# MEGA2560_Rev3e_1.net
KiCad netlist of a schematic drawn in Altium Designer
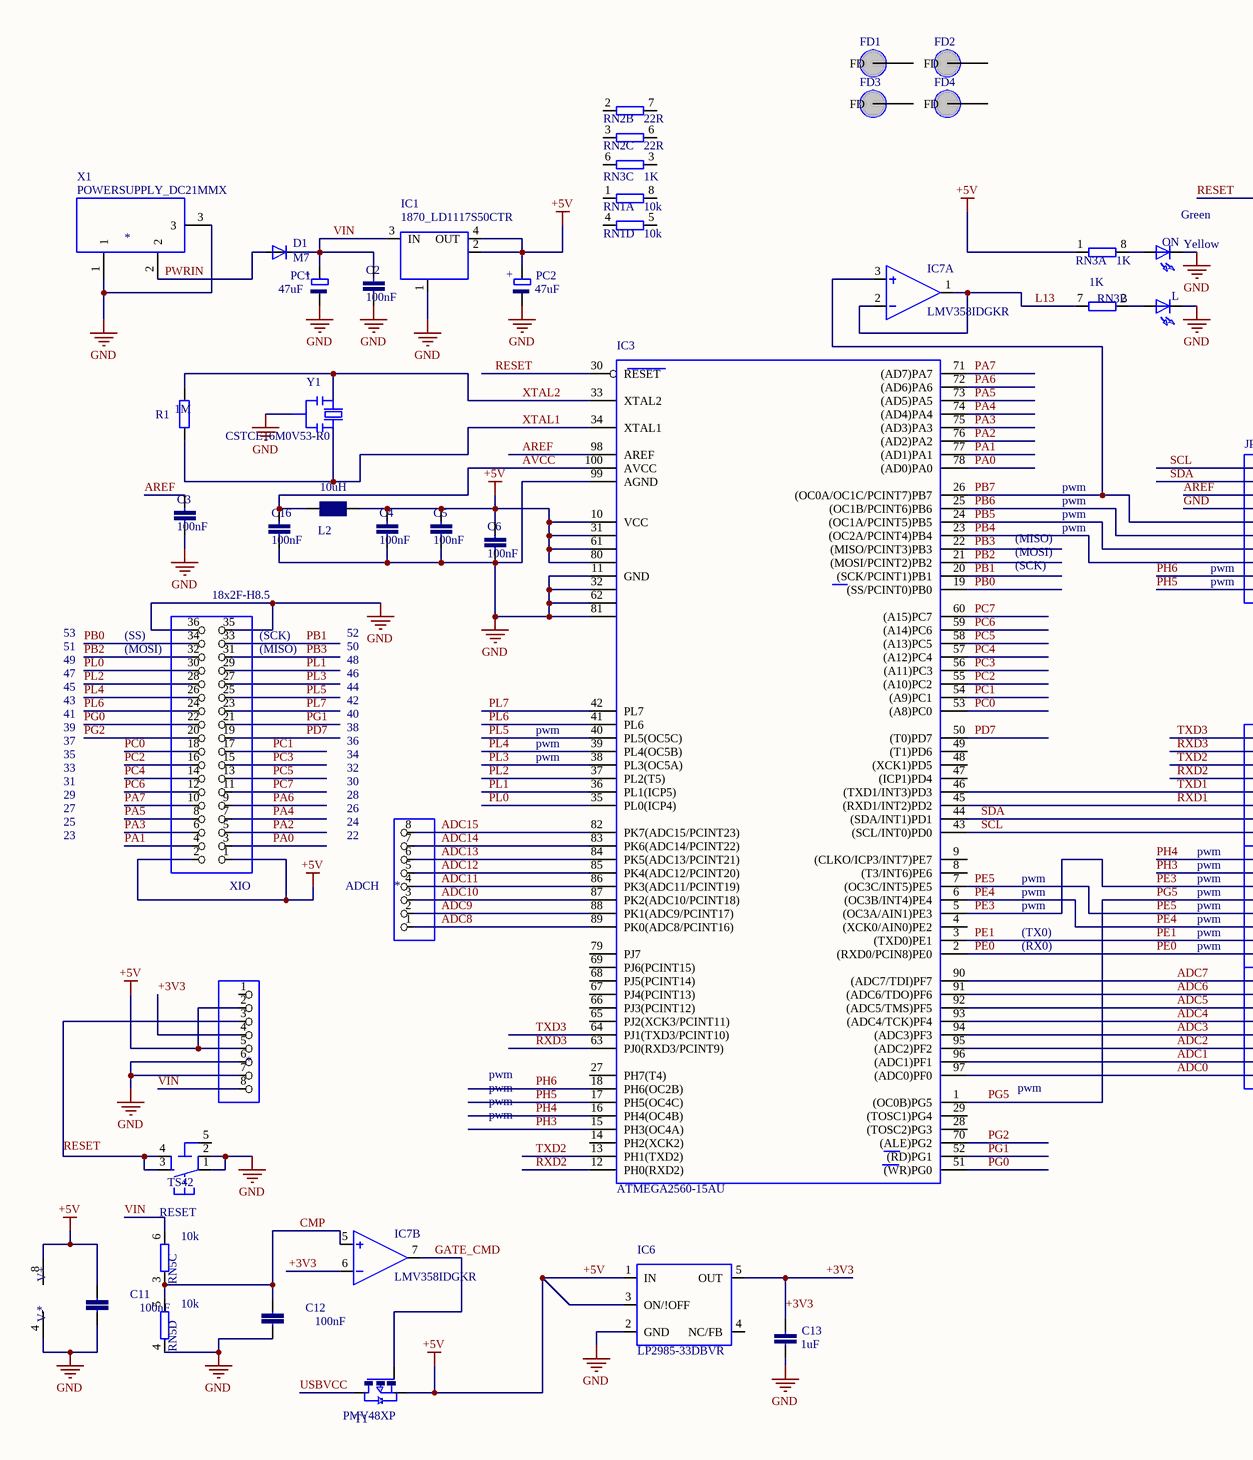
[diagram p0: MEGA2560_Rev3e_1.SchDoc, left]
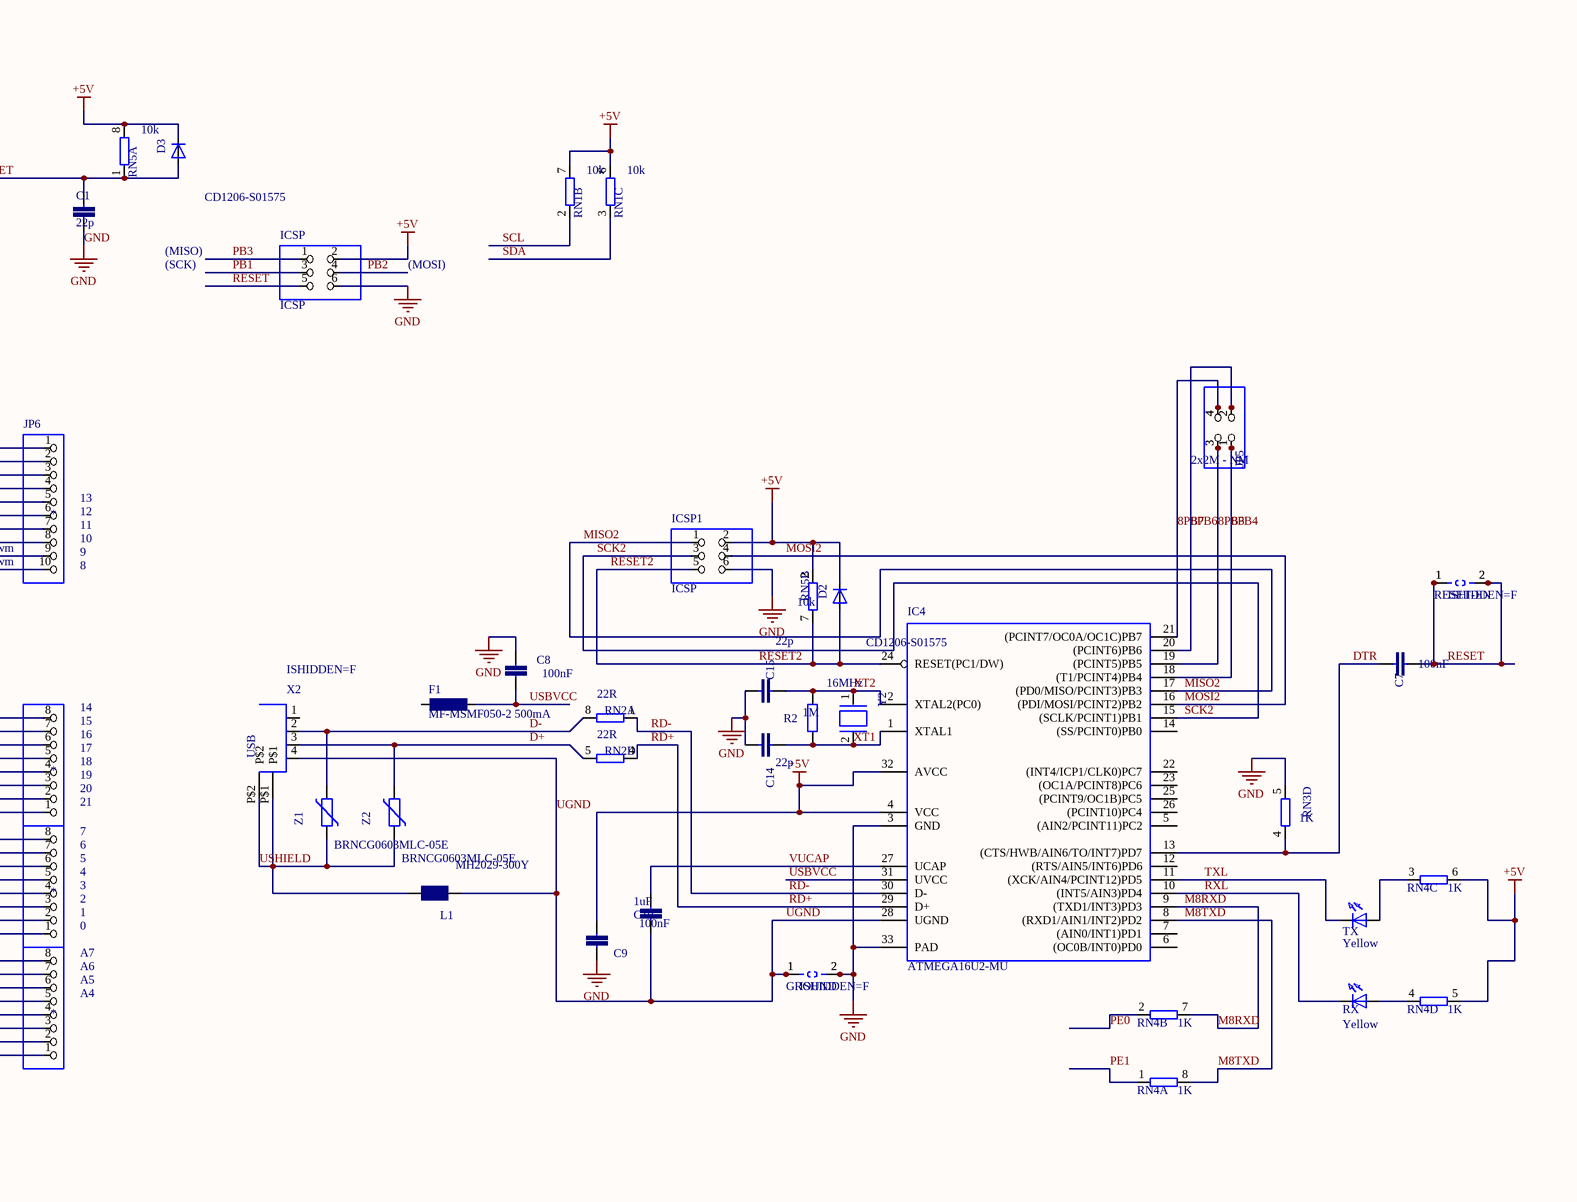
[diagram p1: MEGA2560_Rev3e_1.SchDoc, right]

(export (version "E")
  (design (tool "Eeschema 10.0.6"))
  (components
    (comp (ref "ADCH")
      (value "*")
      (footprint "1X08")
      (libsource (lib "Connettori") (part "0058_FH254-108DF08500V"))
    )
    (comp (ref "ADCL")
      (value "*")
      (footprint "1X08")
      (libsource (lib "Connettori") (part "0058_FH254-108DF08500V"))
    )
    (comp (ref "C1") (value "22p") (footprint "C0603-ROUND") (libsource (lib "") (part "0014_22PF_0603_1")))
    (comp (ref "C2")
      (value "100nF")
      (footprint "C0603-ROUND")
      (libsource (lib "Condensatori") (part "0015_100NF_0603"))
    )
    (comp (ref "C3")
      (value "100nF")
      (footprint "C0603-ROUND")
      (libsource (lib "Condensatori") (part "0015_100NF_0603"))
    )
    (comp (ref "C4")
      (value "100nF")
      (footprint "C0603-ROUND")
      (libsource (lib "Condensatori") (part "0015_100NF_0603"))
    )
    (comp (ref "C5")
      (value "100nF")
      (footprint "C0603-ROUND")
      (libsource (lib "Condensatori") (part "0015_100NF_0603"))
    )
    (comp (ref "C6")
      (value "100nF")
      (footprint "C0603-ROUND")
      (libsource (lib "Condensatori") (part "0015_100NF_0603"))
    )
    (comp (ref "C7")
      (value "100nF")
      (footprint "C0603-ROUND")
      (libsource (lib "") (part "0015_100NF_0603_2"))
    )
    (comp (ref "C8")
      (value "100nF")
      (footprint "C0603-ROUND")
      (libsource (lib "") (part "0015_100NF_0603_3"))
    )
    (comp (ref "C9")
      (value "100nF")
      (footprint "C0603-ROUND")
      (libsource (lib "") (part "0015_100NF_0603_4"))
    )
    (comp (ref "C10")
      (value "1uF")
      (footprint "C0603-ROUND")
      (libsource (lib "") (part "0006_1UF_0603/GRM188R61E105KA12D_1"))
    )
    (comp (ref "C11")
      (value "100nF")
      (footprint "C0603-ROUND")
      (libsource (lib "") (part "0015_100NF_0603_1"))
    )
    (comp (ref "C12")
      (value "100nF")
      (footprint "C0603-ROUND")
      (libsource (lib "") (part "0015_100NF_0603_1"))
    )
    (comp (ref "C13")
      (value "1uF")
      (footprint "C0603-ROUND")
      (libsource (lib "Condensatori") (part "0006_1UF_0603/GRM188R61E105KA12D"))
    )
    (comp (ref "C14")
      (value "22p")
      (footprint "C0603-ROUND")
      (libsource (lib "Condensatori") (part "0014_22PF_0603"))
    )
    (comp (ref "C15")
      (value "22p")
      (footprint "C0603-ROUND")
      (libsource (lib "Condensatori") (part "0014_22PF_0603"))
    )
    (comp (ref "C16")
      (value "100nF")
      (footprint "C0603-ROUND")
      (libsource (lib "Condensatori") (part "0015_100NF_0603"))
    )
    (comp (ref "COMMUNICATION")
      (value "*")
      (footprint "1X08")
      (libsource (lib "Connettori") (part "0058_FH254-108DF08500V"))
    )
    (comp (ref "D1") (value "M7") (footprint "SMB") (libsource (lib "Diodi") (part "0020_M7")))
    (comp (ref "D2")
      (value "CD1206-S01575")
      (footprint "MINIMELF")
      (libsource (lib "Diodi") (part "0012_CD1206-S01575"))
    )
    (comp (ref "D3")
      (value "CD1206-S01575")
      (footprint "MINIMELF")
      (libsource (lib "Diodi") (part "0012_CD1206-S01575"))
    )
    (comp (ref "F1")
      (value "MF-MSMF050-2 500mA")
      (footprint "L1812")
      (libsource (lib "Protezione") (part "0002_MF-MSMF050-2"))
    )
    (comp (ref "FD1")
      (value "FIDUCIALMOUNT")
      (footprint "FIDUCIA-MOUNT")
      (libsource (lib "MEGA2560_Rev3e") (part "FIDUCIALMOUNT"))
    )
    (comp (ref "FD2")
      (value "FIDUCIALMOUNT")
      (footprint "FIDUCIA-MOUNT")
      (libsource (lib "MEGA2560_Rev3e") (part "FIDUCIALMOUNT"))
    )
    (comp (ref "FD3")
      (value "FIDUCIALMOUNT")
      (footprint "FIDUCIA-MOUNT")
      (libsource (lib "MEGA2560_Rev3e") (part "FIDUCIALMOUNT"))
    )
    (comp (ref "FD4")
      (value "FIDUCIALMOUNT")
      (footprint "FIDUCIA-MOUNT")
      (libsource (lib "MEGA2560_Rev3e") (part "FIDUCIALMOUNT"))
    )
    (comp (ref "GROUND") (value "ISHIDDEN=F") (footprint "SJ") (libsource (lib "jumper") (part "SJ")))
    (comp (ref "IC1")
      (value "1870_LD1117S50CTR")
      (footprint "LINEAR_SOT223")
      (libsource (lib "IntegratedCircuits") (part "1870_LD1117S50CTR"))
    )
    (comp (ref "IC3")
      (value "ATMEGA2560-15AU")
      (footprint "TQFP100")
      (libsource (lib "IntegratedCircuits") (part "0023_ATMEGA2560-16AU"))
    )
    (comp (ref "IC4")
      (value "ATMEGA16U2-MU")
      (footprint "MLF32")
      (libsource (lib "IntegratedCircuits") (part "0007_ATMEGA16U2-MUR"))
    )
    (comp (ref "IC6")
      (value "LP2985-33DBVR")
      (footprint "SOT23-DBV")
      (libsource (lib "IntegratedCircuits") (part "0008_TEXLP2985-33DBVR"))
    )
    (comp (ref "IC7")
      (value "LMV358IDGKR")
      (footprint "MSOP08")
      (libsource (lib "") (part "0021_LMV358IDGKR_1"))
    )
    (comp (ref "ICSP")
      (value "ICSP")
      (footprint "2X03")
      (libsource (lib "Connettori") (part "0114_PH254-203DF118A00V"))
    )
    (comp (ref "ICSP1")
      (value "ICSP")
      (footprint "2X03")
      (libsource (lib "Connettori") (part "0114_PH254-203DF118A00V"))
    )
    (comp (ref "JP5") (value "2x2M - NM") (footprint "2X02") (libsource (lib "SmartPrj") (part "PINHD-2X2")))
    (comp (ref "JP6")
      (value "*")
      (footprint "1X10")
      (libsource (lib "Connettori") (part "1216_FH254-110DF08500T30"))
    )
    (comp (ref "L")
      (value "Yellow")
      (footprint "CHIPLED_0805")
      (libsource (lib "") (part "0044_KPT-2012YC_1"))
    )
    (comp (ref "L1")
      (value "MH2029-300Y")
      (footprint "0805")
      (libsource (lib "Protezione") (part "0001_BLM21PG300SN1D_/_MH2029-300Y"))
    )
    (comp (ref "L2")
      (value "10uH")
      (footprint "0805")
      (libsource (lib "Induttanze") (part "0715_CV201210-100K"))
    )
    (comp (ref "ON")
      (value "Green")
      (footprint "CHIPLED_0805")
      (libsource (lib "Opto") (part "0043_KPT-2012SGC"))
    )
    (comp (ref "PC1")
      (value "47uF")
      (footprint "PANASONIC_D")
      (libsource (lib "Condensatori") (part "0113_47UF"))
    )
    (comp (ref "PC2")
      (value "47uF")
      (footprint "PANASONIC_D")
      (libsource (lib "Condensatori") (part "0113_47UF"))
    )
    (comp (ref "POWER")
      (value "*")
      (footprint "1X08")
      (libsource (lib "Connettori") (part "1217_FH254-108DF08500T21"))
    )
    (comp (ref "PWML")
      (value "*")
      (footprint "1X08")
      (libsource (lib "Connettori") (part "1218_FH254-108DF08500T20"))
    )
    (comp (ref "R1")
      (value "1M")
      (footprint "R0603-ROUND")
      (libsource (lib "Resistenze") (part "0004_0603_1M"))
    )
    (comp (ref "R2")
      (value "1M")
      (footprint "R0603-ROUND")
      (libsource (lib "Resistenze") (part "0004_0603_1M"))
    )
    (comp (ref "RESET")
      (value "TS42")
      (footprint "TS42")
      (libsource (lib "Switches") (part "0946_TS42031-160W-TR-7260"))
    )
    (comp (ref "RESET-EN") (value "ISHIDDEN=F") (footprint "SJ") (libsource (lib "jumper") (part "SJ")))
    (comp (ref "RN1")
      (value "10k")
      (footprint "CAY16")
      (libsource (lib "") (part "0016_064R_10K_/_CAY16-103J4LF_4"))
    )
    (comp (ref "RN2")
      (value "22R")
      (footprint "CAY16")
      (libsource (lib "") (part "0003_064R_22R_/_CAY16-220J4LF_1"))
    )
    (comp (ref "RN3")
      (value "1K")
      (footprint "CAY16")
      (libsource (lib "") (part "0005_064R_1K_/_CAY16-102J4LF_6"))
    )
    (comp (ref "RN4")
      (value "1K")
      (footprint "CAY16")
      (libsource (lib "") (part "0005_064R_1K_/_CAY16-102J4LF_5"))
    )
    (comp (ref "RN5")
      (value "10k")
      (footprint "CAY16")
      (libsource (lib "Resistenze") (part "0016_064R_10K_/_CAY16-103J4LF"))
    )
    (comp (ref "RX")
      (value "Yellow")
      (footprint "CHIPLED_0805")
      (libsource (lib "Opto") (part "0044_KPT-2012YC"))
    )
    (comp (ref "T1")
      (value "PMV48XP")
      (footprint "SOT-23")
      (libsource (lib "Transistors") (part "0297_PMV48XP"))
    )
    (comp (ref "TX")
      (value "Yellow")
      (footprint "CHIPLED_0805")
      (libsource (lib "Opto") (part "0044_KPT-2012YC"))
    )
    (comp (ref "X1")
      (value "*")
      (footprint "POWERSUPPLY_DC-21MM")
      (libsource (lib "SmartPrj") (part "POWERSUPPLY_DC21MMX"))
    )
    (comp (ref "X2")
      (value "ISHIDDEN=F")
      (footprint "PN61729")
      (libsource (lib "Connettori") (part "0056_USB-B-S-RA-WT-SPCC"))
    )
    (comp (ref "XIO")
      (value "18x2F-H8.5")
      (footprint "2X18")
      (libsource (lib "Connettori") (part "0060_FH254-218DF08500V"))
    )
    (comp (ref "Y1")
      (value "CSTCE16M0V53-R0")
      (footprint "RESONATOR")
      (libsource (lib "Cristalli") (part "0011_CSTCE16M0V53-R0"))
    )
    (comp (ref "Y2")
      (value "16MHz")
      (footprint "QS")
      (libsource (lib "Cristalli") (part "0019_P011052006_16M"))
    )
    (comp (ref "Z1")
      (value "BRNCG0603MLC-05E")
      (footprint "CT/CN0603")
      (libsource (lib "Protezione") (part "0010_BRNCG0603MLC-05E"))
    )
    (comp (ref "Z2")
      (value "BRNCG0603MLC-05E")
      (footprint "CT/CN0603")
      (libsource (lib "Protezione") (part "0010_BRNCG0603MLC-05E"))
    )
  )
  (nets
    (net (code "1") (name "+5V") (class "Default")
      (node (ref "C11") (pin "2") (pinfunction "2_2") (pintype "passive"))
      (node (ref "C4") (pin "1") (pinfunction "1_1") (pintype "passive"))
      (node (ref "C5") (pin "1") (pinfunction "1_1") (pintype "passive"))
      (node (ref "C6") (pin "1") (pinfunction "1_1") (pintype "passive"))
      (node (ref "C9") (pin "1") (pinfunction "1_1") (pintype "passive"))
      (node (ref "D2") (pin "C") (pinfunction "C_C") (pintype "passive"))
      (node (ref "D3") (pin "C") (pinfunction "C_C") (pintype "passive"))
      (node (ref "IC1") (pin "2") (pinfunction "OUT@1_2") (pintype "passive"))
      (node (ref "IC1") (pin "4") (pinfunction "OUT_4") (pintype "passive"))
      (node (ref "IC3") (pin "10") (pinfunction "VCC_10") (pintype "passive"))
      (node (ref "IC3") (pin "31") (pinfunction "VCC1_31") (pintype "passive"))
      (node (ref "IC3") (pin "61") (pinfunction "VCC2_61") (pintype "passive"))
      (node (ref "IC3") (pin "80") (pinfunction "VCC3_80") (pintype "passive"))
      (node (ref "IC4") (pin "32") (pinfunction "AVCC_32") (pintype "passive"))
      (node (ref "IC4") (pin "4") (pinfunction "VCC_4") (pintype "passive"))
      (node (ref "IC6") (pin "1") (pinfunction "IN_1") (pintype "passive"))
      (node (ref "IC6") (pin "3") (pinfunction "ON/!OFF_3") (pintype "passive"))
      (node (ref "IC7") (pin "8") (pinfunction "V+_8") (pintype "passive"))
      (node (ref "ICSP") (pin "2") (pinfunction "2_2") (pintype "passive"))
      (node (ref "ICSP1") (pin "2") (pinfunction "2_2") (pintype "passive"))
      (node (ref "L2") (pin "2") (pinfunction "2_2") (pintype "passive"))
      (node (ref "PC2") (pin "+") (pinfunction "+_+") (pintype "passive"))
      (node (ref "POWER") (pin "2") (pinfunction "2_2") (pintype "passive"))
      (node (ref "POWER") (pin "5") (pinfunction "5_5") (pintype "passive"))
      (node (ref "RN1") (pin "6") (pinfunction "2_6") (pintype "passive"))
      (node (ref "RN1") (pin "7") (pinfunction "2_7") (pintype "passive"))
      (node (ref "RN3") (pin "1") (pinfunction "1_1") (pintype "passive"))
      (node (ref "RN4") (pin "5") (pinfunction "2_5") (pintype "passive"))
      (node (ref "RN4") (pin "6") (pinfunction "2_6") (pintype "passive"))
      (node (ref "RN5") (pin "2") (pinfunction "1_2") (pintype "passive"))
      (node (ref "RN5") (pin "8") (pinfunction "2_8") (pintype "passive"))
      (node (ref "T1") (pin "2") (pinfunction "S_2") (pintype "passive"))
      (node (ref "XIO") (pin "1") (pinfunction "1_1") (pintype "passive"))
      (node (ref "XIO") (pin "2") (pinfunction "2_2") (pintype "passive"))
    )
    (net (code "2") (name "/+3V3") (class "Default")
      (node (ref "C13") (pin "2") (pinfunction "2_2") (pintype "passive"))
      (node (ref "IC6") (pin "5") (pinfunction "OUT_5") (pintype "passive"))
      (node (ref "IC7") (pin "6") (pinfunction "-IN_6") (pintype "passive"))
      (node (ref "POWER") (pin "4") (pinfunction "4_4") (pintype "passive"))
    )
    (net (code "3") (name "/8PB4") (class "Default")
      (node (ref "IC4") (pin "18") (pinfunction "(T1/PCINT4)PB4_18") (pintype "passive"))
      (node (ref "JP5") (pin "1") (pinfunction "1_1") (pintype "passive"))
    )
    (net (code "4") (name "/8PB5") (class "Default")
      (node (ref "IC4") (pin "19") (pinfunction "(PCINT5)PB5_19") (pintype "passive"))
      (node (ref "JP5") (pin "3") (pinfunction "3_3") (pintype "passive"))
    )
    (net (code "5") (name "/8PB6") (class "Default")
      (node (ref "IC4") (pin "20") (pinfunction "(PCINT6)PB6_20") (pintype "passive"))
      (node (ref "JP5") (pin "2") (pinfunction "2_2") (pintype "passive"))
    )
    (net (code "6") (name "/8PB7") (class "Default")
      (node (ref "IC4") (pin "21") (pinfunction "(PCINT7/OC0A/OC1C)PB7_21") (pintype "passive"))
      (node (ref "JP5") (pin "4") (pinfunction "4_4") (pintype "passive"))
    )
    (net (code "7") (name "/ADC0") (class "Default")
      (node (ref "ADCL") (pin "1") (pinfunction "1_1") (pintype "passive"))
      (node (ref "IC3") (pin "97") (pinfunction "(ADC0)PF0_97") (pintype "passive"))
    )
    (net (code "8") (name "/ADC1") (class "Default")
      (node (ref "ADCL") (pin "2") (pinfunction "2_2") (pintype "passive"))
      (node (ref "IC3") (pin "96") (pinfunction "(ADC1)PF1_96") (pintype "passive"))
    )
    (net (code "9") (name "/ADC2") (class "Default")
      (node (ref "ADCL") (pin "3") (pinfunction "3_3") (pintype "passive"))
      (node (ref "IC3") (pin "95") (pinfunction "(ADC2)PF2_95") (pintype "passive"))
    )
    (net (code "10") (name "/ADC3") (class "Default")
      (node (ref "ADCL") (pin "4") (pinfunction "4_4") (pintype "passive"))
      (node (ref "IC3") (pin "94") (pinfunction "(ADC3)PF3_94") (pintype "passive"))
    )
    (net (code "11") (name "/ADC4") (class "Default")
      (node (ref "ADCL") (pin "5") (pinfunction "5_5") (pintype "passive"))
      (node (ref "IC3") (pin "93") (pinfunction "(ADC4/TCK)PF4_93") (pintype "passive"))
    )
    (net (code "12") (name "/ADC5") (class "Default")
      (node (ref "ADCL") (pin "6") (pinfunction "6_6") (pintype "passive"))
      (node (ref "IC3") (pin "92") (pinfunction "(ADC5/TMS)PF5_92") (pintype "passive"))
    )
    (net (code "13") (name "/ADC6") (class "Default")
      (node (ref "ADCL") (pin "7") (pinfunction "7_7") (pintype "passive"))
      (node (ref "IC3") (pin "91") (pinfunction "(ADC6/TDO)PF6_91") (pintype "passive"))
    )
    (net (code "14") (name "/ADC7") (class "Default")
      (node (ref "ADCL") (pin "8") (pinfunction "8_8") (pintype "passive"))
      (node (ref "IC3") (pin "90") (pinfunction "(ADC7/TDI)PF7_90") (pintype "passive"))
    )
    (net (code "15") (name "/ADC8") (class "Default")
      (node (ref "ADCH") (pin "1") (pinfunction "1_1") (pintype "passive"))
      (node (ref "IC3") (pin "89") (pinfunction "PK0(ADC8/PCINT16)_89") (pintype "passive"))
    )
    (net (code "16") (name "/ADC9") (class "Default")
      (node (ref "ADCH") (pin "2") (pinfunction "2_2") (pintype "passive"))
      (node (ref "IC3") (pin "88") (pinfunction "PK1(ADC9/PCINT17)_88") (pintype "passive"))
    )
    (net (code "17") (name "/ADC10") (class "Default")
      (node (ref "ADCH") (pin "3") (pinfunction "3_3") (pintype "passive"))
      (node (ref "IC3") (pin "87") (pinfunction "PK2(ADC10/PCINT18)_87") (pintype "passive"))
    )
    (net (code "18") (name "/ADC11") (class "Default")
      (node (ref "ADCH") (pin "4") (pinfunction "4_4") (pintype "passive"))
      (node (ref "IC3") (pin "86") (pinfunction "PK3(ADC11/PCINT19)_86") (pintype "passive"))
    )
    (net (code "19") (name "/ADC12") (class "Default")
      (node (ref "ADCH") (pin "5") (pinfunction "5_5") (pintype "passive"))
      (node (ref "IC3") (pin "85") (pinfunction "PK4(ADC12/PCINT20)_85") (pintype "passive"))
    )
    (net (code "20") (name "/ADC13") (class "Default")
      (node (ref "ADCH") (pin "6") (pinfunction "6_6") (pintype "passive"))
      (node (ref "IC3") (pin "84") (pinfunction "PK5(ADC13/PCINT21)_84") (pintype "passive"))
    )
    (net (code "21") (name "/ADC14") (class "Default")
      (node (ref "ADCH") (pin "7") (pinfunction "7_7") (pintype "passive"))
      (node (ref "IC3") (pin "83") (pinfunction "PK6(ADC14/PCINT22)_83") (pintype "passive"))
    )
    (net (code "22") (name "/ADC15") (class "Default")
      (node (ref "ADCH") (pin "8") (pinfunction "8_8") (pintype "passive"))
      (node (ref "IC3") (pin "82") (pinfunction "PK7(ADC15/PCINT23)_82") (pintype "passive"))
    )
    (net (code "23") (name "/AREF") (class "Default")
      (node (ref "C3") (pin "1") (pinfunction "1_1") (pintype "passive"))
      (node (ref "IC3") (pin "98") (pinfunction "AREF_98") (pintype "passive"))
      (node (ref "JP6") (pin "3") (pinfunction "3_3") (pintype "passive"))
    )
    (net (code "24") (name "/AVCC") (class "Default")
      (node (ref "C16") (pin "1") (pinfunction "1_1") (pintype "passive"))
      (node (ref "IC3") (pin "100") (pinfunction "AVCC_100") (pintype "passive"))
      (node (ref "L2") (pin "1") (pinfunction "1_1") (pintype "passive"))
    )
    (net (code "25") (name "/CMP") (class "Default")
      (node (ref "C12") (pin "2") (pinfunction "2_2") (pintype "passive"))
      (node (ref "IC7") (pin "5") (pinfunction "+IN_5") (pintype "passive"))
      (node (ref "RN5") (pin "3") (pinfunction "1_3") (pintype "passive"))
      (node (ref "RN5") (pin "5") (pinfunction "2_5") (pintype "passive"))
    )
    (net (code "26") (name "/D+") (class "Default")
      (node (ref "RN2") (pin "5") (pinfunction "2_5") (pintype "passive"))
      (node (ref "X2") (pin "3") (pinfunction "3_3") (pintype "passive"))
      (node (ref "Z2") (pin "2") (pinfunction "2_2") (pintype "passive"))
    )
    (net (code "27") (name "/D-") (class "Default")
      (node (ref "RN2") (pin "8") (pinfunction "2_8") (pintype "passive"))
      (node (ref "X2") (pin "2") (pinfunction "2_2") (pintype "passive"))
      (node (ref "Z1") (pin "2") (pinfunction "2_2") (pintype "passive"))
    )
    (net (code "28") (name "/DTR") (class "Default")
      (node (ref "C7") (pin "1") (pinfunction "1_1") (pintype "passive"))
      (node (ref "IC4") (pin "13") (pinfunction "(CTS/HWB/AIN6/TO/INT7)PD7_13") (pintype "passive"))
      (node (ref "RN3") (pin "4") (pinfunction "1_4") (pintype "passive"))
    )
    (net (code "29") (name "/GATE_CMD") (class "Default")
      (node (ref "IC7") (pin "7") (pinfunction "OUT_7") (pintype "passive"))
      (node (ref "T1") (pin "3") (pinfunction "G_3") (pintype "passive"))
    )
    (net (code "30") (name "/L13") (class "Default")
      (node (ref "IC7") (pin "1") (pinfunction "OUT_1") (pintype "passive"))
      (node (ref "IC7") (pin "2") (pinfunction "-IN_2") (pintype "passive"))
      (node (ref "RN3") (pin "7") (pinfunction "2_7") (pintype "passive"))
    )
    (net (code "31") (name "/M8RXD") (class "Default")
      (node (ref "IC4") (pin "9") (pinfunction "(TXD1/INT3)PD3_9") (pintype "passive"))
      (node (ref "RN4") (pin "7") (pinfunction "2_7") (pintype "passive"))
    )
    (net (code "32") (name "/M8TXD") (class "Default")
      (node (ref "IC4") (pin "8") (pinfunction "(RXD1/AIN1/INT2)PD2_8") (pintype "passive"))
      (node (ref "RN4") (pin "8") (pinfunction "2_8") (pintype "passive"))
    )
    (net (code "33") (name "/MISO2") (class "Default")
      (node (ref "IC4") (pin "17") (pinfunction "(PD0/MISO/PCINT3)PB3_17") (pintype "passive"))
      (node (ref "ICSP1") (pin "1") (pinfunction "1_1") (pintype "passive"))
    )
    (net (code "34") (name "/MOSI2") (class "Default")
      (node (ref "IC4") (pin "16") (pinfunction "(PDI/MOSI/PCINT2)PB2_16") (pintype "passive"))
      (node (ref "ICSP1") (pin "4") (pinfunction "4_4") (pintype "passive"))
    )
    (net (code "35") (name "/PA0") (class "Default")
      (node (ref "IC3") (pin "78") (pinfunction "(AD0)PA0_78") (pintype "passive"))
      (node (ref "XIO") (pin "3") (pinfunction "3_3") (pintype "passive"))
    )
    (net (code "36") (name "/PA1") (class "Default")
      (node (ref "IC3") (pin "77") (pinfunction "(AD1)PA1_77") (pintype "passive"))
      (node (ref "XIO") (pin "4") (pinfunction "4_4") (pintype "passive"))
    )
    (net (code "37") (name "/PA2") (class "Default")
      (node (ref "IC3") (pin "76") (pinfunction "(AD2)PA2_76") (pintype "passive"))
      (node (ref "XIO") (pin "5") (pinfunction "5_5") (pintype "passive"))
    )
    (net (code "38") (name "/PA3") (class "Default")
      (node (ref "IC3") (pin "75") (pinfunction "(AD3)PA3_75") (pintype "passive"))
      (node (ref "XIO") (pin "6") (pinfunction "6_6") (pintype "passive"))
    )
    (net (code "39") (name "/PA4") (class "Default")
      (node (ref "IC3") (pin "74") (pinfunction "(AD4)PA4_74") (pintype "passive"))
      (node (ref "XIO") (pin "7") (pinfunction "7_7") (pintype "passive"))
    )
    (net (code "40") (name "/PA5") (class "Default")
      (node (ref "IC3") (pin "73") (pinfunction "(AD5)PA5_73") (pintype "passive"))
      (node (ref "XIO") (pin "8") (pinfunction "8_8") (pintype "passive"))
    )
    (net (code "41") (name "/PA6") (class "Default")
      (node (ref "IC3") (pin "72") (pinfunction "(AD6)PA6_72") (pintype "passive"))
      (node (ref "XIO") (pin "9") (pinfunction "9_9") (pintype "passive"))
    )
    (net (code "42") (name "/PA7") (class "Default")
      (node (ref "IC3") (pin "71") (pinfunction "(AD7)PA7_71") (pintype "passive"))
      (node (ref "XIO") (pin "10") (pinfunction "10_10") (pintype "passive"))
    )
    (net (code "43") (name "/PB0") (class "Default")
      (node (ref "IC3") (pin "19") (pinfunction "(SS/PCINT0)PB0_19") (pintype "passive"))
      (node (ref "XIO") (pin "34") (pinfunction "34_34") (pintype "passive"))
    )
    (net (code "44") (name "/PB1") (class "Default")
      (node (ref "IC3") (pin "20") (pinfunction "(SCK/PCINT1)PB1_20") (pintype "passive"))
      (node (ref "ICSP") (pin "3") (pinfunction "3_3") (pintype "passive"))
      (node (ref "XIO") (pin "33") (pinfunction "33_33") (pintype "passive"))
    )
    (net (code "45") (name "/PB2") (class "Default")
      (node (ref "IC3") (pin "21") (pinfunction "(MOSI/PCINT2)PB2_21") (pintype "passive"))
      (node (ref "ICSP") (pin "4") (pinfunction "4_4") (pintype "passive"))
      (node (ref "XIO") (pin "32") (pinfunction "32_32") (pintype "passive"))
    )
    (net (code "46") (name "/PB3") (class "Default")
      (node (ref "IC3") (pin "22") (pinfunction "(MISO/PCINT3)PB3_22") (pintype "passive"))
      (node (ref "ICSP") (pin "1") (pinfunction "1_1") (pintype "passive"))
      (node (ref "XIO") (pin "31") (pinfunction "31_31") (pintype "passive"))
    )
    (net (code "47") (name "/PB4") (class "Default")
      (node (ref "IC3") (pin "23") (pinfunction "(OC2A/PCINT4)PB4_23") (pintype "passive"))
      (node (ref "JP6") (pin "8") (pinfunction "8_8") (pintype "passive"))
    )
    (net (code "48") (name "/PB5") (class "Default")
      (node (ref "IC3") (pin "24") (pinfunction "(OC1A/PCINT5)PB5_24") (pintype "passive"))
      (node (ref "JP6") (pin "7") (pinfunction "7_7") (pintype "passive"))
    )
    (net (code "49") (name "/PB6") (class "Default")
      (node (ref "IC3") (pin "25") (pinfunction "(OC1B/PCINT6)PB6_25") (pintype "passive"))
      (node (ref "JP6") (pin "6") (pinfunction "6_6") (pintype "passive"))
    )
    (net (code "50") (name "/PB7") (class "Default")
      (node (ref "IC3") (pin "26") (pinfunction "(OC0A/OC1C/PCINT7)PB7_26") (pintype "passive"))
      (node (ref "IC7") (pin "3") (pinfunction "+IN_3") (pintype "passive"))
      (node (ref "JP6") (pin "5") (pinfunction "5_5") (pintype "passive"))
    )
    (net (code "51") (name "/PC0") (class "Default")
      (node (ref "IC3") (pin "53") (pinfunction "(A8)PC0_53") (pintype "passive"))
      (node (ref "XIO") (pin "18") (pinfunction "18_18") (pintype "passive"))
    )
    (net (code "52") (name "/PC1") (class "Default")
      (node (ref "IC3") (pin "54") (pinfunction "(A9)PC1_54") (pintype "passive"))
      (node (ref "XIO") (pin "17") (pinfunction "17_17") (pintype "passive"))
    )
    (net (code "53") (name "/PC2") (class "Default")
      (node (ref "IC3") (pin "55") (pinfunction "(A10)PC2_55") (pintype "passive"))
      (node (ref "XIO") (pin "16") (pinfunction "16_16") (pintype "passive"))
    )
    (net (code "54") (name "/PC3") (class "Default")
      (node (ref "IC3") (pin "56") (pinfunction "(A11)PC3_56") (pintype "passive"))
      (node (ref "XIO") (pin "15") (pinfunction "15_15") (pintype "passive"))
    )
    (net (code "55") (name "/PC4") (class "Default")
      (node (ref "IC3") (pin "57") (pinfunction "(A12)PC4_57") (pintype "passive"))
      (node (ref "XIO") (pin "14") (pinfunction "14_14") (pintype "passive"))
    )
    (net (code "56") (name "/PC5") (class "Default")
      (node (ref "IC3") (pin "58") (pinfunction "(A13)PC5_58") (pintype "passive"))
      (node (ref "XIO") (pin "13") (pinfunction "13_13") (pintype "passive"))
    )
    (net (code "57") (name "/PC6") (class "Default")
      (node (ref "IC3") (pin "59") (pinfunction "(A14)PC6_59") (pintype "passive"))
      (node (ref "XIO") (pin "12") (pinfunction "12_12") (pintype "passive"))
    )
    (net (code "58") (name "/PC7") (class "Default")
      (node (ref "IC3") (pin "60") (pinfunction "(A15)PC7_60") (pintype "passive"))
      (node (ref "XIO") (pin "11") (pinfunction "11_11") (pintype "passive"))
    )
    (net (code "59") (name "/PD7") (class "Default")
      (node (ref "IC3") (pin "50") (pinfunction "(T0)PD7_50") (pintype "passive"))
      (node (ref "XIO") (pin "19") (pinfunction "19_19") (pintype "passive"))
    )
    (net (code "60") (name "/PE0") (class "Default")
      (node (ref "IC3") (pin "2") (pinfunction "(RXD0/PCIN8)PE0_2") (pintype "passive"))
      (node (ref "PWML") (pin "1") (pinfunction "1_1") (pintype "passive"))
      (node (ref "RN4") (pin "2") (pinfunction "1_2") (pintype "passive"))
    )
    (net (code "61") (name "/PE1") (class "Default")
      (node (ref "IC3") (pin "3") (pinfunction "(TXD0)PE1_3") (pintype "passive"))
      (node (ref "PWML") (pin "2") (pinfunction "2_2") (pintype "passive"))
      (node (ref "RN4") (pin "1") (pinfunction "1_1") (pintype "passive"))
    )
    (net (code "62") (name "/PE3") (class "Default")
      (node (ref "IC3") (pin "5") (pinfunction "(OC3A/AIN1)PE3_5") (pintype "passive"))
      (node (ref "PWML") (pin "6") (pinfunction "6_6") (pintype "passive"))
    )
    (net (code "63") (name "/PE4") (class "Default")
      (node (ref "IC3") (pin "6") (pinfunction "(OC3B/INT4)PE4_6") (pintype "passive"))
      (node (ref "PWML") (pin "3") (pinfunction "3_3") (pintype "passive"))
    )
    (net (code "64") (name "/PE5") (class "Default")
      (node (ref "IC3") (pin "7") (pinfunction "(OC3C/INT5)PE5_7") (pintype "passive"))
      (node (ref "PWML") (pin "4") (pinfunction "4_4") (pintype "passive"))
    )
    (net (code "65") (name "/PG0") (class "Default")
      (node (ref "IC3") (pin "51") (pinfunction "(WR)PG0_51") (pintype "passive"))
      (node (ref "XIO") (pin "22") (pinfunction "22_22") (pintype "passive"))
    )
    (net (code "66") (name "/PG1") (class "Default")
      (node (ref "IC3") (pin "52") (pinfunction "(RD)PG1_52") (pintype "passive"))
      (node (ref "XIO") (pin "21") (pinfunction "21_21") (pintype "passive"))
    )
    (net (code "67") (name "/PG2") (class "Default")
      (node (ref "IC3") (pin "70") (pinfunction "(ALE)PG2_70") (pintype "passive"))
      (node (ref "XIO") (pin "20") (pinfunction "20_20") (pintype "passive"))
    )
    (net (code "68") (name "/PG5") (class "Default")
      (node (ref "IC3") (pin "1") (pinfunction "(OC0B)PG5_1") (pintype "passive"))
      (node (ref "PWML") (pin "5") (pinfunction "5_5") (pintype "passive"))
    )
    (net (code "69") (name "/PH3") (class "Default")
      (node (ref "IC3") (pin "15") (pinfunction "PH3(OC4A)_15") (pintype "passive"))
      (node (ref "PWML") (pin "7") (pinfunction "7_7") (pintype "passive"))
    )
    (net (code "70") (name "/PH4") (class "Default")
      (node (ref "IC3") (pin "16") (pinfunction "PH4(OC4B)_16") (pintype "passive"))
      (node (ref "PWML") (pin "8") (pinfunction "8_8") (pintype "passive"))
    )
    (net (code "71") (name "/PH5") (class "Default")
      (node (ref "IC3") (pin "17") (pinfunction "PH5(OC4C)_17") (pintype "passive"))
      (node (ref "JP6") (pin "10") (pinfunction "10_10") (pintype "passive"))
    )
    (net (code "72") (name "/PH6") (class "Default")
      (node (ref "IC3") (pin "18") (pinfunction "PH6(OC2B)_18") (pintype "passive"))
      (node (ref "JP6") (pin "9") (pinfunction "9_9") (pintype "passive"))
    )
    (net (code "73") (name "/PL0") (class "Default")
      (node (ref "IC3") (pin "35") (pinfunction "PL0(ICP4)_35") (pintype "passive"))
      (node (ref "XIO") (pin "30") (pinfunction "30_30") (pintype "passive"))
    )
    (net (code "74") (name "/PL1") (class "Default")
      (node (ref "IC3") (pin "36") (pinfunction "PL1(ICP5)_36") (pintype "passive"))
      (node (ref "XIO") (pin "29") (pinfunction "29_29") (pintype "passive"))
    )
    (net (code "75") (name "/PL2") (class "Default")
      (node (ref "IC3") (pin "37") (pinfunction "PL2(T5)_37") (pintype "passive"))
      (node (ref "XIO") (pin "28") (pinfunction "28_28") (pintype "passive"))
    )
    (net (code "76") (name "/PL3") (class "Default")
      (node (ref "IC3") (pin "38") (pinfunction "PL3(OC5A)_38") (pintype "passive"))
      (node (ref "XIO") (pin "27") (pinfunction "27_27") (pintype "passive"))
    )
    (net (code "77") (name "/PL4") (class "Default")
      (node (ref "IC3") (pin "39") (pinfunction "PL4(OC5B)_39") (pintype "passive"))
      (node (ref "XIO") (pin "26") (pinfunction "26_26") (pintype "passive"))
    )
    (net (code "78") (name "/PL5") (class "Default")
      (node (ref "IC3") (pin "40") (pinfunction "PL5(OC5C)_40") (pintype "passive"))
      (node (ref "XIO") (pin "25") (pinfunction "25_25") (pintype "passive"))
    )
    (net (code "79") (name "/PL6") (class "Default")
      (node (ref "IC3") (pin "41") (pinfunction "PL6_41") (pintype "passive"))
      (node (ref "XIO") (pin "24") (pinfunction "24_24") (pintype "passive"))
    )
    (net (code "80") (name "/PL7") (class "Default")
      (node (ref "IC3") (pin "42") (pinfunction "PL7_42") (pintype "passive"))
      (node (ref "XIO") (pin "23") (pinfunction "23_23") (pintype "passive"))
    )
    (net (code "81") (name "/PWRIN") (class "Default")
      (node (ref "D1") (pin "A") (pinfunction "A_A") (pintype "passive"))
      (node (ref "X1") (pin "2") (pinfunction "2_2") (pintype "passive"))
    )
    (net (code "82") (name "/RD+") (class "Default")
      (node (ref "IC4") (pin "29") (pinfunction "D+_29") (pintype "passive"))
      (node (ref "RN2") (pin "4") (pinfunction "1_4") (pintype "passive"))
    )
    (net (code "83") (name "/RD-") (class "Default")
      (node (ref "IC4") (pin "30") (pinfunction "D-_30") (pintype "passive"))
      (node (ref "RN2") (pin "1") (pinfunction "1_1") (pintype "passive"))
    )
    (net (code "84") (name "/RESET") (class "Default")
      (node (ref "C1") (pin "1") (pinfunction "1_1") (pintype "passive"))
      (node (ref "C7") (pin "2") (pinfunction "2_2") (pintype "passive"))
      (node (ref "D3") (pin "A") (pinfunction "A_A") (pintype "passive"))
      (node (ref "IC3") (pin "30") (pinfunction "RESET_30") (pintype "passive"))
      (node (ref "ICSP") (pin "5") (pinfunction "5_5") (pintype "passive"))
      (node (ref "POWER") (pin "3") (pinfunction "3_3") (pintype "passive"))
      (node (ref "RESET") (pin "3") (pinfunction "3_3") (pintype "passive"))
      (node (ref "RESET") (pin "4") (pinfunction "4_4") (pintype "passive"))
      (node (ref "RESET-EN") (pin "1") (pinfunction "1_1") (pintype "passive"))
      (node (ref "RESET-EN") (pin "2") (pinfunction "2_2") (pintype "passive"))
      (node (ref "RN5") (pin "1") (pinfunction "1_1") (pintype "passive"))
    )
    (net (code "85") (name "/RESET2") (class "Default")
      (node (ref "D2") (pin "A") (pinfunction "A_A") (pintype "passive"))
      (node (ref "IC4") (pin "24") (pinfunction "RESET(PC1/DW)_24") (pintype "passive"))
      (node (ref "ICSP1") (pin "5") (pinfunction "5_5") (pintype "passive"))
      (node (ref "RN5") (pin "7") (pinfunction "2_7") (pintype "passive"))
    )
    (net (code "86") (name "/RXD1") (class "Default")
      (node (ref "COMMUNICATION") (pin "3") (pinfunction "3_3") (pintype "passive"))
      (node (ref "IC3") (pin "45") (pinfunction "(RXD1/INT2)PD2_45") (pintype "passive"))
    )
    (net (code "87") (name "/RXD2") (class "Default")
      (node (ref "COMMUNICATION") (pin "5") (pinfunction "5_5") (pintype "passive"))
      (node (ref "IC3") (pin "12") (pinfunction "PH0(RXD2)_12") (pintype "passive"))
    )
    (net (code "88") (name "/RXD3") (class "Default")
      (node (ref "COMMUNICATION") (pin "7") (pinfunction "7_7") (pintype "passive"))
      (node (ref "IC3") (pin "63") (pinfunction "PJ0(RXD3/PCINT9)_63") (pintype "passive"))
    )
    (net (code "89") (name "/RXL") (class "Default")
      (node (ref "IC4") (pin "10") (pinfunction "(INT5/AIN3)PD4_10") (pintype "passive"))
      (node (ref "RX") (pin "C") (pinfunction "C_C") (pintype "passive"))
    )
    (net (code "90") (name "/SCK2") (class "Default")
      (node (ref "IC4") (pin "15") (pinfunction "(SCLK/PCINT1)PB1_15") (pintype "passive"))
      (node (ref "ICSP1") (pin "3") (pinfunction "3_3") (pintype "passive"))
    )
    (net (code "91") (name "/SCL") (class "Default")
      (node (ref "COMMUNICATION") (pin "1") (pinfunction "1_1") (pintype "passive"))
      (node (ref "IC3") (pin "43") (pinfunction "(SCL/INT0)PD0_43") (pintype "passive"))
      (node (ref "JP6") (pin "1") (pinfunction "1_1") (pintype "passive"))
      (node (ref "RN1") (pin "2") (pinfunction "1_2") (pintype "passive"))
    )
    (net (code "92") (name "/SDA") (class "Default")
      (node (ref "COMMUNICATION") (pin "2") (pinfunction "2_2") (pintype "passive"))
      (node (ref "IC3") (pin "44") (pinfunction "(SDA/INT1)PD1_44") (pintype "passive"))
      (node (ref "JP6") (pin "2") (pinfunction "2_2") (pintype "passive"))
      (node (ref "RN1") (pin "3") (pinfunction "1_3") (pintype "passive"))
    )
    (net (code "93") (name "/TXD1") (class "Default")
      (node (ref "COMMUNICATION") (pin "4") (pinfunction "4_4") (pintype "passive"))
      (node (ref "IC3") (pin "46") (pinfunction "(TXD1/INT3)PD3_46") (pintype "passive"))
    )
    (net (code "94") (name "/TXD2") (class "Default")
      (node (ref "COMMUNICATION") (pin "6") (pinfunction "6_6") (pintype "passive"))
      (node (ref "IC3") (pin "13") (pinfunction "PH1(TXD2)_13") (pintype "passive"))
    )
    (net (code "95") (name "/TXD3") (class "Default")
      (node (ref "COMMUNICATION") (pin "8") (pinfunction "8_8") (pintype "passive"))
      (node (ref "IC3") (pin "64") (pinfunction "PJ1(TXD3/PCINT10)_64") (pintype "passive"))
    )
    (net (code "96") (name "/TXL") (class "Default")
      (node (ref "IC4") (pin "11") (pinfunction "(XCK/AIN4/PCINT12)PD5_11") (pintype "passive"))
      (node (ref "TX") (pin "C") (pinfunction "C_C") (pintype "passive"))
    )
    (net (code "97") (name "/UGND") (class "Default")
      (node (ref "C10") (pin "2") (pinfunction "2_2") (pintype "passive"))
      (node (ref "GROUND") (pin "1") (pinfunction "1_1") (pintype "passive"))
      (node (ref "IC4") (pin "28") (pinfunction "UGND_28") (pintype "passive"))
      (node (ref "L1") (pin "1") (pinfunction "1_1") (pintype "passive"))
      (node (ref "X2") (pin "4") (pinfunction "4_4") (pintype "passive"))
    )
    (net (code "98") (name "/USBVCC") (class "Default")
      (node (ref "C8") (pin "1") (pinfunction "1_1") (pintype "passive"))
      (node (ref "F1") (pin "1") (pinfunction "1_1") (pintype "passive"))
      (node (ref "IC4") (pin "31") (pinfunction "UVCC_31") (pintype "passive"))
      (node (ref "T1") (pin "1") (pinfunction "D_1") (pintype "passive"))
    )
    (net (code "99") (name "/USHIELD") (class "Default")
      (node (ref "L1") (pin "2") (pinfunction "2_2") (pintype "passive"))
      (node (ref "X2") (pin "P$1") (pinfunction "P$1_P$1") (pintype "passive"))
      (node (ref "X2") (pin "P$2") (pinfunction "P$2_P$2") (pintype "passive"))
      (node (ref "Z1") (pin "1") (pinfunction "1_1") (pintype "passive"))
      (node (ref "Z2") (pin "1") (pinfunction "1_1") (pintype "passive"))
    )
    (net (code "100") (name "/VIN") (class "Default")
      (node (ref "C2") (pin "1") (pinfunction "1_1") (pintype "passive"))
      (node (ref "D1") (pin "C") (pinfunction "C_C") (pintype "passive"))
      (node (ref "IC1") (pin "3") (pinfunction "IN_3") (pintype "passive"))
      (node (ref "PC1") (pin "+") (pinfunction "+_+") (pintype "passive"))
      (node (ref "POWER") (pin "8") (pinfunction "8_8") (pintype "passive"))
      (node (ref "RN5") (pin "6") (pinfunction "2_6") (pintype "passive"))
    )
    (net (code "101") (name "/VUCAP") (class "Default")
      (node (ref "C10") (pin "1") (pinfunction "1_1") (pintype "passive"))
      (node (ref "IC4") (pin "27") (pinfunction "UCAP_27") (pintype "passive"))
    )
    (net (code "102") (name "/XT1") (class "Default")
      (node (ref "C14") (pin "1") (pinfunction "1_1") (pintype "passive"))
      (node (ref "IC4") (pin "1") (pinfunction "XTAL1_1") (pintype "passive"))
      (node (ref "R2") (pin "1") (pinfunction "1_1") (pintype "passive"))
      (node (ref "Y2") (pin "2") (pinfunction "2_2") (pintype "passive"))
    )
    (net (code "103") (name "/XT2") (class "Default")
      (node (ref "C15") (pin "1") (pinfunction "1_1") (pintype "passive"))
      (node (ref "IC4") (pin "2") (pinfunction "XTAL2(PC0)_2") (pintype "passive"))
      (node (ref "R2") (pin "2") (pinfunction "2_2") (pintype "passive"))
      (node (ref "Y2") (pin "1") (pinfunction "1_1") (pintype "passive"))
    )
    (net (code "104") (name "/XTAL1") (class "Default")
      (node (ref "IC3") (pin "34") (pinfunction "XTAL1_34") (pintype "passive"))
      (node (ref "R1") (pin "1") (pinfunction "1_1") (pintype "passive"))
      (node (ref "Y1") (pin "3") (pinfunction "3_3") (pintype "passive"))
    )
    (net (code "105") (name "/XTAL2") (class "Default")
      (node (ref "IC3") (pin "33") (pinfunction "XTAL2_33") (pintype "passive"))
      (node (ref "R1") (pin "2") (pinfunction "2_2") (pintype "passive"))
      (node (ref "Y1") (pin "1") (pinfunction "1_1") (pintype "passive"))
    )
    (net (code "106") (name "GND") (class "Default")
      (node (ref "C1") (pin "2") (pinfunction "2_2") (pintype "passive"))
      (node (ref "C11") (pin "1") (pinfunction "1_1") (pintype "passive"))
      (node (ref "C12") (pin "1") (pinfunction "1_1") (pintype "passive"))
      (node (ref "C13") (pin "1") (pinfunction "1_1") (pintype "passive"))
      (node (ref "C14") (pin "2") (pinfunction "2_2") (pintype "passive"))
      (node (ref "C15") (pin "2") (pinfunction "2_2") (pintype "passive"))
      (node (ref "C16") (pin "2") (pinfunction "2_2") (pintype "passive"))
      (node (ref "C2") (pin "2") (pinfunction "2_2") (pintype "passive"))
      (node (ref "C3") (pin "2") (pinfunction "2_2") (pintype "passive"))
      (node (ref "C4") (pin "2") (pinfunction "2_2") (pintype "passive"))
      (node (ref "C5") (pin "2") (pinfunction "2_2") (pintype "passive"))
      (node (ref "C6") (pin "2") (pinfunction "2_2") (pintype "passive"))
      (node (ref "C8") (pin "2") (pinfunction "2_2") (pintype "passive"))
      (node (ref "C9") (pin "2") (pinfunction "2_2") (pintype "passive"))
      (node (ref "GROUND") (pin "2") (pinfunction "2_2") (pintype "passive"))
      (node (ref "IC1") (pin "1") (pinfunction "GND/ADJ_1") (pintype "passive"))
      (node (ref "IC3") (pin "11") (pinfunction "GND_11") (pintype "passive"))
      (node (ref "IC3") (pin "32") (pinfunction "GND1_32") (pintype "passive"))
      (node (ref "IC3") (pin "62") (pinfunction "GND2_62") (pintype "passive"))
      (node (ref "IC3") (pin "81") (pinfunction "GND3_81") (pintype "passive"))
      (node (ref "IC3") (pin "99") (pinfunction "AGND_99") (pintype "passive"))
      (node (ref "IC4") (pin "3") (pinfunction "GND_3") (pintype "passive"))
      (node (ref "IC4") (pin "33") (pinfunction "PAD_33") (pintype "passive"))
      (node (ref "IC6") (pin "2") (pinfunction "GND_2") (pintype "passive"))
      (node (ref "IC7") (pin "4") (pinfunction "V-_4") (pintype "passive"))
      (node (ref "ICSP") (pin "6") (pinfunction "6_6") (pintype "passive"))
      (node (ref "ICSP1") (pin "6") (pinfunction "6_6") (pintype "passive"))
      (node (ref "JP6") (pin "4") (pinfunction "4_4") (pintype "passive"))
      (node (ref "L") (pin "C") (pinfunction "C_C") (pintype "passive"))
      (node (ref "ON") (pin "C") (pinfunction "C_C") (pintype "passive"))
      (node (ref "PC1") (pin "-") (pinfunction "-_-") (pintype "passive"))
      (node (ref "PC2") (pin "-") (pinfunction "-_-") (pintype "passive"))
      (node (ref "POWER") (pin "6") (pinfunction "6_6") (pintype "passive"))
      (node (ref "POWER") (pin "7") (pinfunction "7_7") (pintype "passive"))
      (node (ref "RESET") (pin "1") (pinfunction "1_1") (pintype "passive"))
      (node (ref "RESET") (pin "2") (pinfunction "2_2") (pintype "passive"))
      (node (ref "RN3") (pin "5") (pinfunction "2_5") (pintype "passive"))
      (node (ref "RN5") (pin "4") (pinfunction "1_4") (pintype "passive"))
      (node (ref "X1") (pin "1") (pinfunction "1_1") (pintype "passive"))
      (node (ref "X1") (pin "3") (pinfunction "3_3") (pintype "passive"))
      (node (ref "XIO") (pin "35") (pinfunction "35_35") (pintype "passive"))
      (node (ref "XIO") (pin "36") (pinfunction "36_36") (pintype "passive"))
      (node (ref "Y1") (pin "2") (pinfunction "2_2") (pintype "passive"))
    )
    (net (code "107") (name "Net-(RN3A-2)") (class "Default")
      (node (ref "ON") (pin "A") (pinfunction "A_A") (pintype "passive"))
      (node (ref "RN3") (pin "8") (pinfunction "2_8") (pintype "passive"))
    )
    (net (code "108") (name "Net-(RN3B-1)") (class "Default")
      (node (ref "L") (pin "A") (pinfunction "A_A") (pintype "passive"))
      (node (ref "RN3") (pin "2") (pinfunction "1_2") (pintype "passive"))
    )
    (net (code "109") (name "Net-(RN4C-1)") (class "Default")
      (node (ref "RN4") (pin "3") (pinfunction "1_3") (pintype "passive"))
      (node (ref "TX") (pin "A") (pinfunction "A_A") (pintype "passive"))
    )
    (net (code "110") (name "Net-(RN4D-1)") (class "Default")
      (node (ref "RN4") (pin "4") (pinfunction "1_4") (pintype "passive"))
      (node (ref "RX") (pin "A") (pinfunction "A_A") (pintype "passive"))
    )
    (net (code "111") (name "unconnected-(F1-Pad2)") (class "Default")
      (node (ref "F1") (pin "2") (pinfunction "2_2") (pintype "passive"))
    )
    (net (code "112") (name "unconnected-(FD1-FD-Pad)") (class "Default")
      (node (ref "FD1") (pin "") (pinfunction "FD_") (pintype "passive"))
    )
    (net (code "113") (name "unconnected-(FD2-FD-Pad)") (class "Default")
      (node (ref "FD2") (pin "") (pinfunction "FD_") (pintype "passive"))
    )
    (net (code "114") (name "unconnected-(FD3-FD-Pad)") (class "Default")
      (node (ref "FD3") (pin "") (pinfunction "FD_") (pintype "passive"))
    )
    (net (code "115") (name "unconnected-(FD4-FD-Pad)") (class "Default")
      (node (ref "FD4") (pin "") (pinfunction "FD_") (pintype "passive"))
    )
    (net (code "116") (name "unconnected-(IC3-(CLKO{slash}ICP3{slash}INT7)PE7-Pad9)") (class "Default")
      (node (ref "IC3") (pin "9") (pinfunction "(CLKO/ICP3/INT7)PE7_9") (pintype "passive"))
    )
    (net (code "117") (name "unconnected-(IC3-(ICP1)PD4-Pad47)") (class "Default")
      (node (ref "IC3") (pin "47") (pinfunction "(ICP1)PD4_47") (pintype "passive"))
    )
    (net (code "118") (name "unconnected-(IC3-(T1)PD6-Pad49)") (class "Default")
      (node (ref "IC3") (pin "49") (pinfunction "(T1)PD6_49") (pintype "passive"))
    )
    (net (code "119") (name "unconnected-(IC3-(T3{slash}INT6)PE6-Pad8)") (class "Default")
      (node (ref "IC3") (pin "8") (pinfunction "(T3/INT6)PE6_8") (pintype "passive"))
    )
    (net (code "120") (name "unconnected-(IC3-(TOSC1)PG4-Pad29)") (class "Default")
      (node (ref "IC3") (pin "29") (pinfunction "(TOSC1)PG4_29") (pintype "passive"))
    )
    (net (code "121") (name "unconnected-(IC3-(TOSC2)PG3-Pad28)") (class "Default")
      (node (ref "IC3") (pin "28") (pinfunction "(TOSC2)PG3_28") (pintype "passive"))
    )
    (net (code "122") (name "unconnected-(IC3-(XCK0{slash}AIN0)PE2-Pad4)") (class "Default")
      (node (ref "IC3") (pin "4") (pinfunction "(XCK0/AIN0)PE2_4") (pintype "passive"))
    )
    (net (code "123") (name "unconnected-(IC3-(XCK1)PD5-Pad48)") (class "Default")
      (node (ref "IC3") (pin "48") (pinfunction "(XCK1)PD5_48") (pintype "passive"))
    )
    (net (code "124") (name "unconnected-(IC3-PH2(XCK2)-Pad14)") (class "Default")
      (node (ref "IC3") (pin "14") (pinfunction "PH2(XCK2)_14") (pintype "passive"))
    )
    (net (code "125") (name "unconnected-(IC3-PH7(T4)-Pad27)") (class "Default")
      (node (ref "IC3") (pin "27") (pinfunction "PH7(T4)_27") (pintype "passive"))
    )
    (net (code "126") (name "unconnected-(IC3-PJ2(XCK3{slash}PCINT11)-Pad65)") (class "Default")
      (node (ref "IC3") (pin "65") (pinfunction "PJ2(XCK3/PCINT11)_65") (pintype "passive"))
    )
    (net (code "127") (name "unconnected-(IC3-PJ3(PCINT12)-Pad66)") (class "Default")
      (node (ref "IC3") (pin "66") (pinfunction "PJ3(PCINT12)_66") (pintype "passive"))
    )
    (net (code "128") (name "unconnected-(IC3-PJ4(PCINT13)-Pad67)") (class "Default")
      (node (ref "IC3") (pin "67") (pinfunction "PJ4(PCINT13)_67") (pintype "passive"))
    )
    (net (code "129") (name "unconnected-(IC3-PJ5(PCINT14)-Pad68)") (class "Default")
      (node (ref "IC3") (pin "68") (pinfunction "PJ5(PCINT14)_68") (pintype "passive"))
    )
    (net (code "130") (name "unconnected-(IC3-PJ6(PCINT15)-Pad69)") (class "Default")
      (node (ref "IC3") (pin "69") (pinfunction "PJ6(PCINT15)_69") (pintype "passive"))
    )
    (net (code "131") (name "unconnected-(IC3-PJ7-Pad79)") (class "Default")
      (node (ref "IC3") (pin "79") (pinfunction "PJ7_79") (pintype "passive"))
    )
    (net (code "132") (name "unconnected-(IC4-(AIN0{slash}INT1)PD1-Pad7)") (class "Default")
      (node (ref "IC4") (pin "7") (pinfunction "(AIN0/INT1)PD1_7") (pintype "passive"))
    )
    (net (code "133") (name "unconnected-(IC4-(AIN2{slash}PCINT11)PC2-Pad5)") (class "Default")
      (node (ref "IC4") (pin "5") (pinfunction "(AIN2/PCINT11)PC2_5") (pintype "passive"))
    )
    (net (code "134") (name "unconnected-(IC4-(INT4{slash}ICP1{slash}CLK0)PC7-Pad22)") (class "Default")
      (node (ref "IC4") (pin "22") (pinfunction "(INT4/ICP1/CLK0)PC7_22") (pintype "passive"))
    )
    (net (code "135") (name "unconnected-(IC4-(OC0B{slash}INT0)PD0-Pad6)") (class "Default")
      (node (ref "IC4") (pin "6") (pinfunction "(OC0B/INT0)PD0_6") (pintype "passive"))
    )
    (net (code "136") (name "unconnected-(IC4-(OC1A{slash}PCINT8)PC6-Pad23)") (class "Default")
      (node (ref "IC4") (pin "23") (pinfunction "(OC1A/PCINT8)PC6_23") (pintype "passive"))
    )
    (net (code "137") (name "unconnected-(IC4-(PCINT9{slash}OC1B)PC5-Pad25)") (class "Default")
      (node (ref "IC4") (pin "25") (pinfunction "(PCINT9/OC1B)PC5_25") (pintype "passive"))
    )
    (net (code "138") (name "unconnected-(IC4-(PCINT10)PC4-Pad26)") (class "Default")
      (node (ref "IC4") (pin "26") (pinfunction "(PCINT10)PC4_26") (pintype "passive"))
    )
    (net (code "139") (name "unconnected-(IC4-(RTS{slash}AIN5{slash}INT6)PD6-Pad12)") (class "Default")
      (node (ref "IC4") (pin "12") (pinfunction "(RTS/AIN5/INT6)PD6_12") (pintype "passive"))
    )
    (net (code "140") (name "unconnected-(IC4-(SS{slash}PCINT0)PB0-Pad14)") (class "Default")
      (node (ref "IC4") (pin "14") (pinfunction "(SS/PCINT0)PB0_14") (pintype "passive"))
    )
    (net (code "141") (name "unconnected-(IC6-NC{slash}FB-Pad4)") (class "Default")
      (node (ref "IC6") (pin "4") (pinfunction "NC/FB_4") (pintype "passive"))
    )
    (net (code "142") (name "unconnected-(POWER-Pad1)") (class "Default")
      (node (ref "POWER") (pin "1") (pinfunction "1_1") (pintype "passive"))
    )
    (net (code "143") (name "unconnected-(RESET-5-GND-Pad5)") (class "Default")
      (node (ref "RESET") (pin "5") (pinfunction "5-GND_5") (pintype "passive"))
    )
    (net (code "144") (name "unconnected-(RN1-Pad1)") (class "Default")
      (node (ref "RN1") (pin "1") (pinfunction "1_1") (pintype "passive"))
    )
    (net (code "145") (name "unconnected-(RN1A-2-Pad8)") (class "Default")
      (node (ref "RN1") (pin "8") (pinfunction "2_8") (pintype "passive"))
    )
    (net (code "146") (name "unconnected-(RN1D-1-Pad4)") (class "Default")
      (node (ref "RN1") (pin "4") (pinfunction "1_4") (pintype "passive"))
    )
    (net (code "147") (name "unconnected-(RN1D-2-Pad5)") (class "Default")
      (node (ref "RN1") (pin "5") (pinfunction "2_5") (pintype "passive"))
    )
    (net (code "148") (name "unconnected-(RN2B-1-Pad2)") (class "Default")
      (node (ref "RN2") (pin "2") (pinfunction "1_2") (pintype "passive"))
    )
    (net (code "149") (name "unconnected-(RN2B-2-Pad7)") (class "Default")
      (node (ref "RN2") (pin "7") (pinfunction "2_7") (pintype "passive"))
    )
    (net (code "150") (name "unconnected-(RN2C-1-Pad3)") (class "Default")
      (node (ref "RN2") (pin "3") (pinfunction "1_3") (pintype "passive"))
    )
    (net (code "151") (name "unconnected-(RN2C-2-Pad6)") (class "Default")
      (node (ref "RN2") (pin "6") (pinfunction "2_6") (pintype "passive"))
    )
    (net (code "152") (name "unconnected-(RN3C-1-Pad3)") (class "Default")
      (node (ref "RN3") (pin "3") (pinfunction "1_3") (pintype "passive"))
    )
    (net (code "153") (name "unconnected-(RN3C-2-Pad6)") (class "Default")
      (node (ref "RN3") (pin "6") (pinfunction "2_6") (pintype "passive"))
    )
    (net (code "154") (name "unconnected-(X2-Pad1)") (class "Default")
      (node (ref "X2") (pin "1") (pinfunction "1_1") (pintype "passive"))
    )
  )
)
